# RelayDriver.net
KiCad netlist of a schematic drawn in Altium Designer
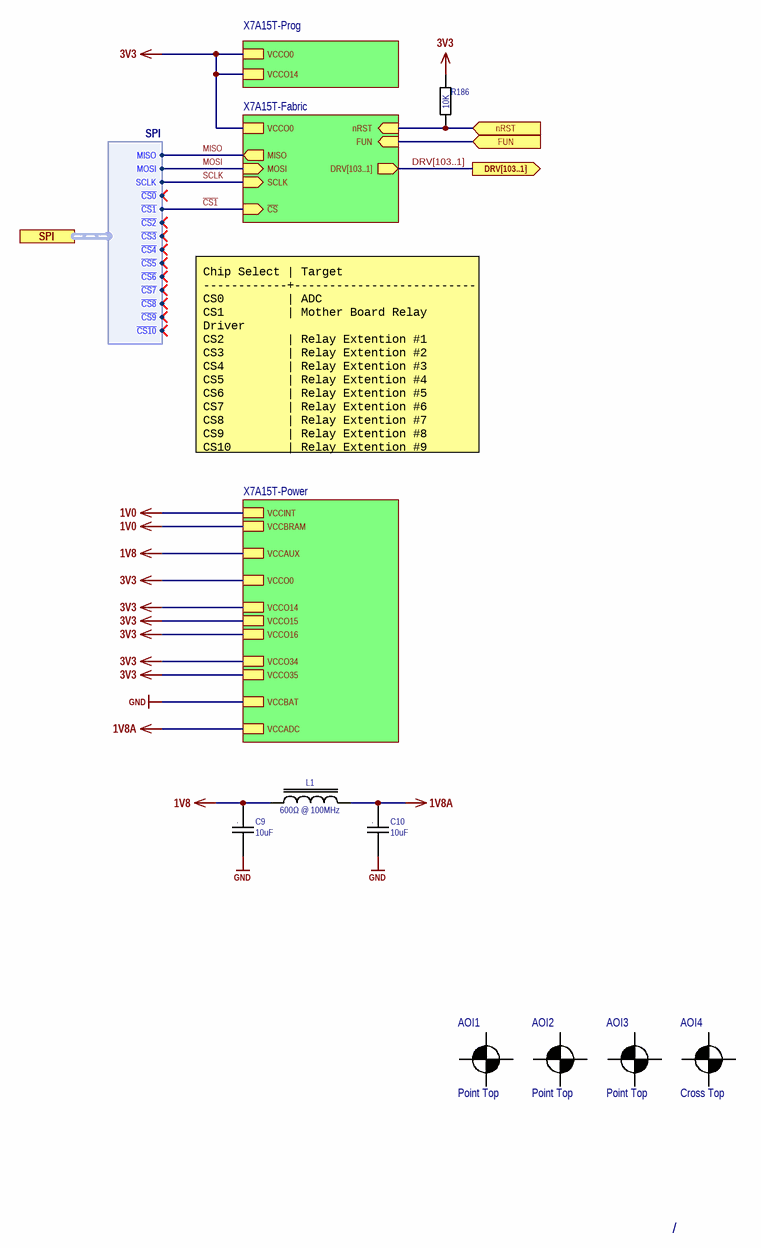
[diagram p0: RelayDriver.SchDoc]

(export (version "E")
  (design (tool "Eeschema 10.0.6"))
  (components
    (comp (ref "AOI1")
      (value "AOI")
      (footprint "Fiducial Point")
      (description "Assembly AOI")
      (fields (field (name "SHAPE") "Point Top") (field (name "13. CREATED DATE/NAME") "AUG2018/Hören"))
      (libsource (lib "PCB-Tester-Board-V1") (part "Fiducial"))
    )
    (comp (ref "AOI2")
      (value "AOI")
      (footprint "Fiducial Point")
      (description "Assembly AOI")
      (fields (field (name "SHAPE") "Point Top") (field (name "13. CREATED DATE/NAME") "AUG2018/Hören"))
      (libsource (lib "PCB-Tester-Board-V1") (part "Fiducial"))
    )
    (comp (ref "AOI3")
      (value "AOI")
      (footprint "Fiducial Point")
      (description "Assembly AOI")
      (fields (field (name "SHAPE") "Point Top") (field (name "13. CREATED DATE/NAME") "AUG2018/Hören"))
      (libsource (lib "PCB-Tester-Board-V1") (part "Fiducial"))
    )
    (comp (ref "AOI4")
      (value "AOI")
      (footprint "Fiducial Cross")
      (description "Assembly AOI")
      (fields (field (name "SHAPE") "Cross Top") (field (name "13. CREATED DATE/NAME") "AUG2018/Hören"))
      (libsource (lib "PCB-Tester-Board-V1") (part "Fiducial"))
    )
    (comp (ref "C9")
      (value "10uF")
      (footprint "C0805 Reflow")
      (description "CAP CER 10UF 10V X7R 0805")
      (fields
        (field (name "TOLERANCE") "±10%")
        (field (name "02. DISTRIBUTOR PART NUMBER") "1276-1764-6-ND")
        (field (name "13. CREATED DATE/NAME") "AUG2018/Hören")
      )
      (libsource (lib "chickenfood") (part "C"))
    )
    (comp (ref "C10")
      (value "10uF")
      (footprint "C0805 Reflow")
      (description "CAP CER 10UF 10V X7R 0805")
      (fields
        (field (name "TOLERANCE") "±10%")
        (field (name "02. DISTRIBUTOR PART NUMBER") "1276-1764-6-ND")
        (field (name "13. CREATED DATE/NAME") "AUG2018/Hören")
      )
      (libsource (lib "chickenfood") (part "C"))
    )
    (comp (ref "L1")
      (value "L")
      (footprint "FB0805")
      (description "FERRITE BEAD 600 OHM 0805 1LN")
      (fields
        (field (name "NOMINAL IMPEDANCE") "600Ω @ 100MHz")
        (field (name "02. DISTRIBUTOR PART NUMBER") "732-1620-6-ND")
        (field (name "07. MANUFACTURER  PART NUMBER") "742792040")
        (field (name "13. CREATED DATE/NAME") "AUG2018/Hören")
      )
      (libsource (lib "chickenfood") (part "FB"))
    )
    (comp (ref "R186")
      (value "10K")
      (footprint "R0402 Reflow")
      (description "RES SMD 10K OHM 1% 1/16W 0402")
      (fields
        (field (name "TOLERANCE") "±1%")
        (field (name "02. DISTRIBUTOR PART NUMBER") "311-10.0KLRDKR-ND")
        (field (name "13. CREATED DATE/NAME") "AUG2018/Hören")
      )
      (libsource (lib "chickenfood") (part "R"))
    )
  )
  (nets
    (net (code "111") (name "/nRST") (class "Default")
      (node (ref "R186") (pin "2") (pinfunction "2_2") (pintype "passive"))
    )
    (net (code "114") (name "1V8") (class "Default")
      (node (ref "C9") (pin "1") (pinfunction "1_1") (pintype "passive"))
      (node (ref "L1") (pin "1") (pinfunction "1_1") (pintype "passive"))
    )
    (net (code "115") (name "1V8A") (class "Default")
      (node (ref "C10") (pin "1") (pinfunction "1_1") (pintype "passive"))
      (node (ref "L1") (pin "2") (pinfunction "2_2") (pintype "passive"))
    )
    (net (code "116") (name "3V3") (class "Default")
      (node (ref "R186") (pin "1") (pinfunction "1_1") (pintype "passive"))
    )
    (net (code "117") (name "GND") (class "Default")
      (node (ref "C10") (pin "2") (pinfunction "2_2") (pintype "passive"))
      (node (ref "C9") (pin "2") (pinfunction "2_2") (pintype "passive"))
    )
  )
)
